# LaunchPad_Connectors.net
KiCad netlist of a schematic drawn in Altium Designer
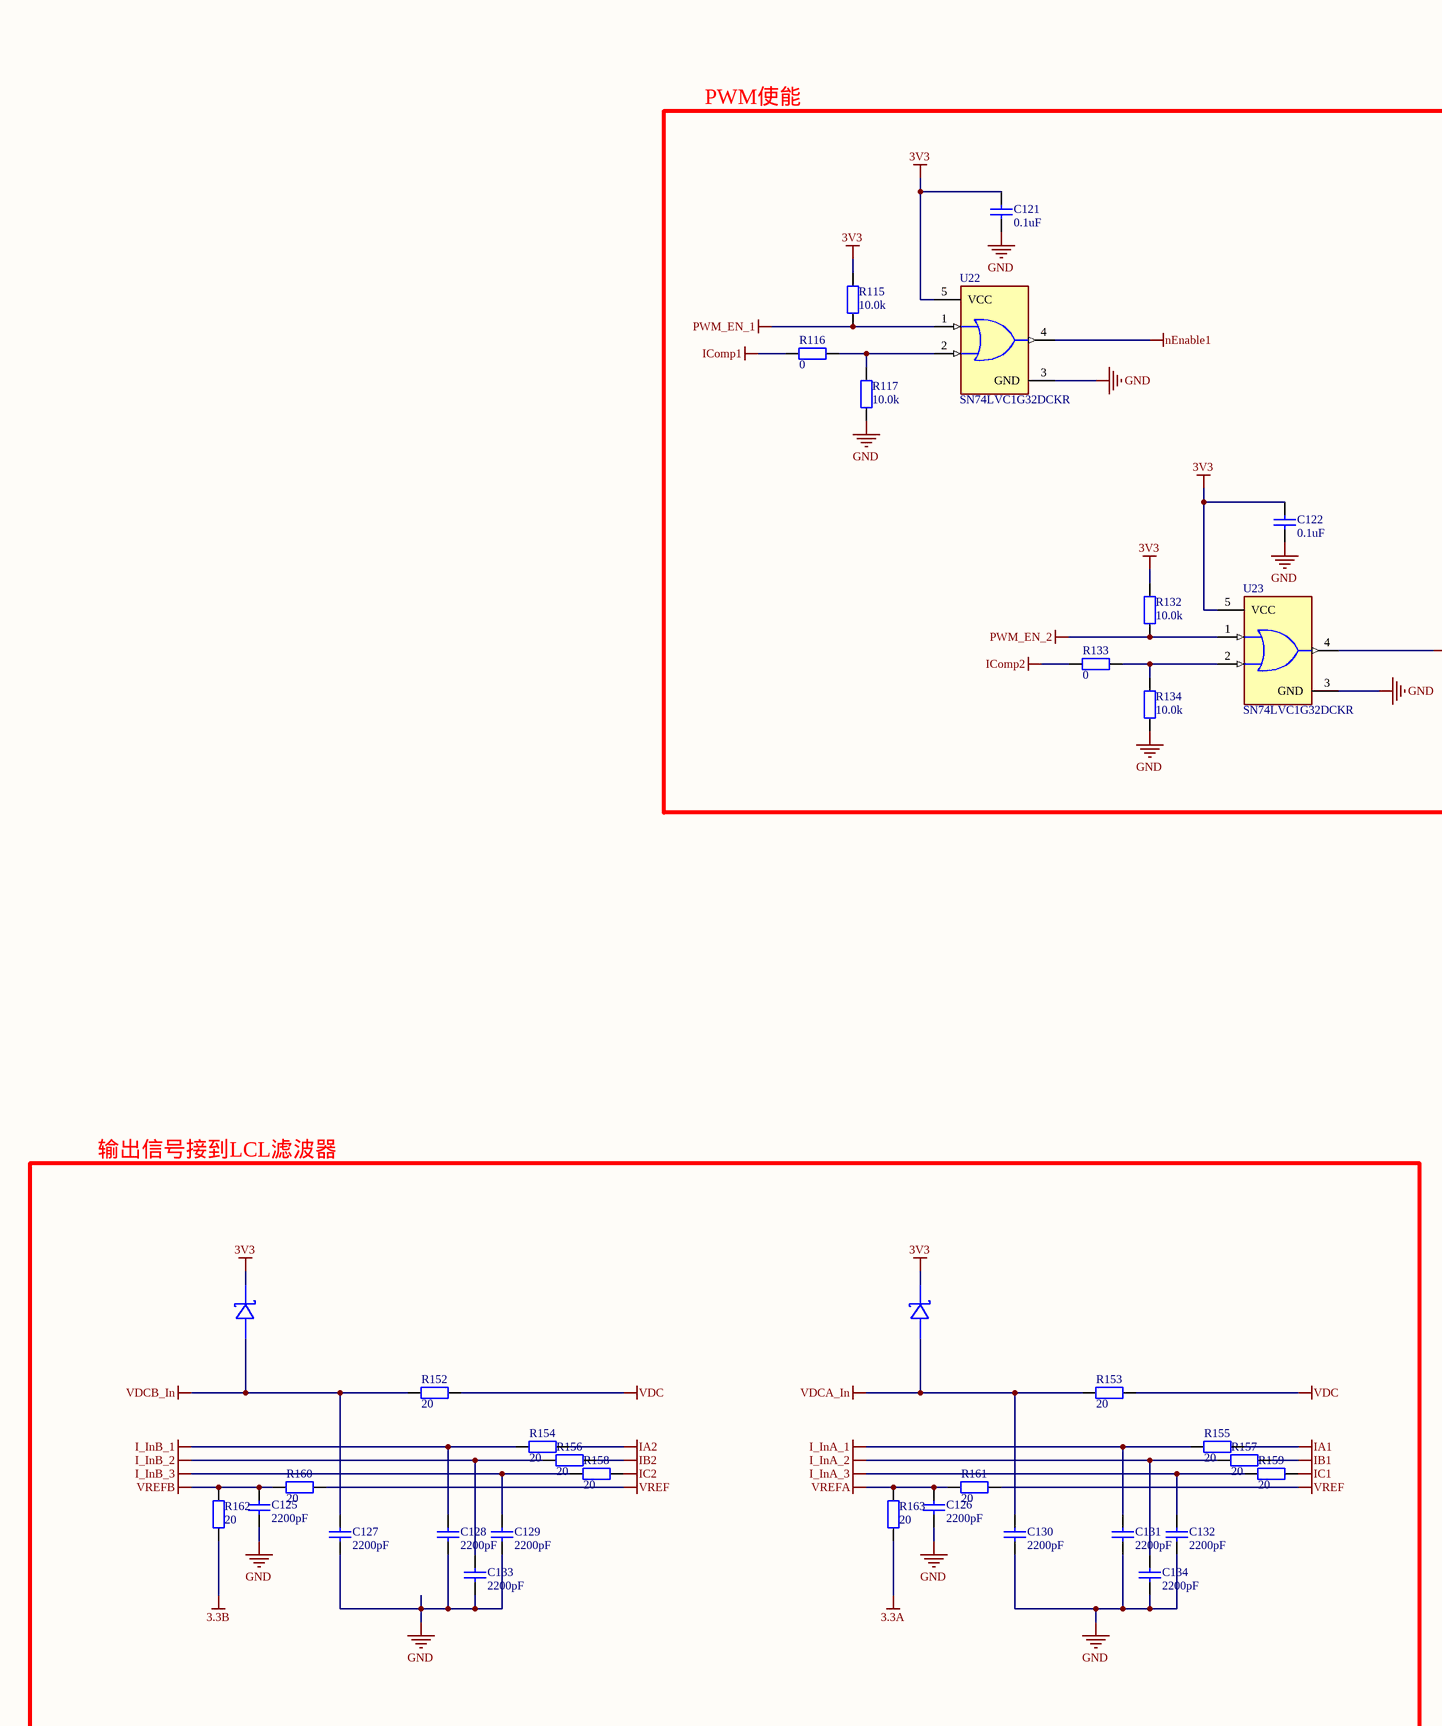
[diagram p0: LaunchPad Connectors.SchDoc, left]
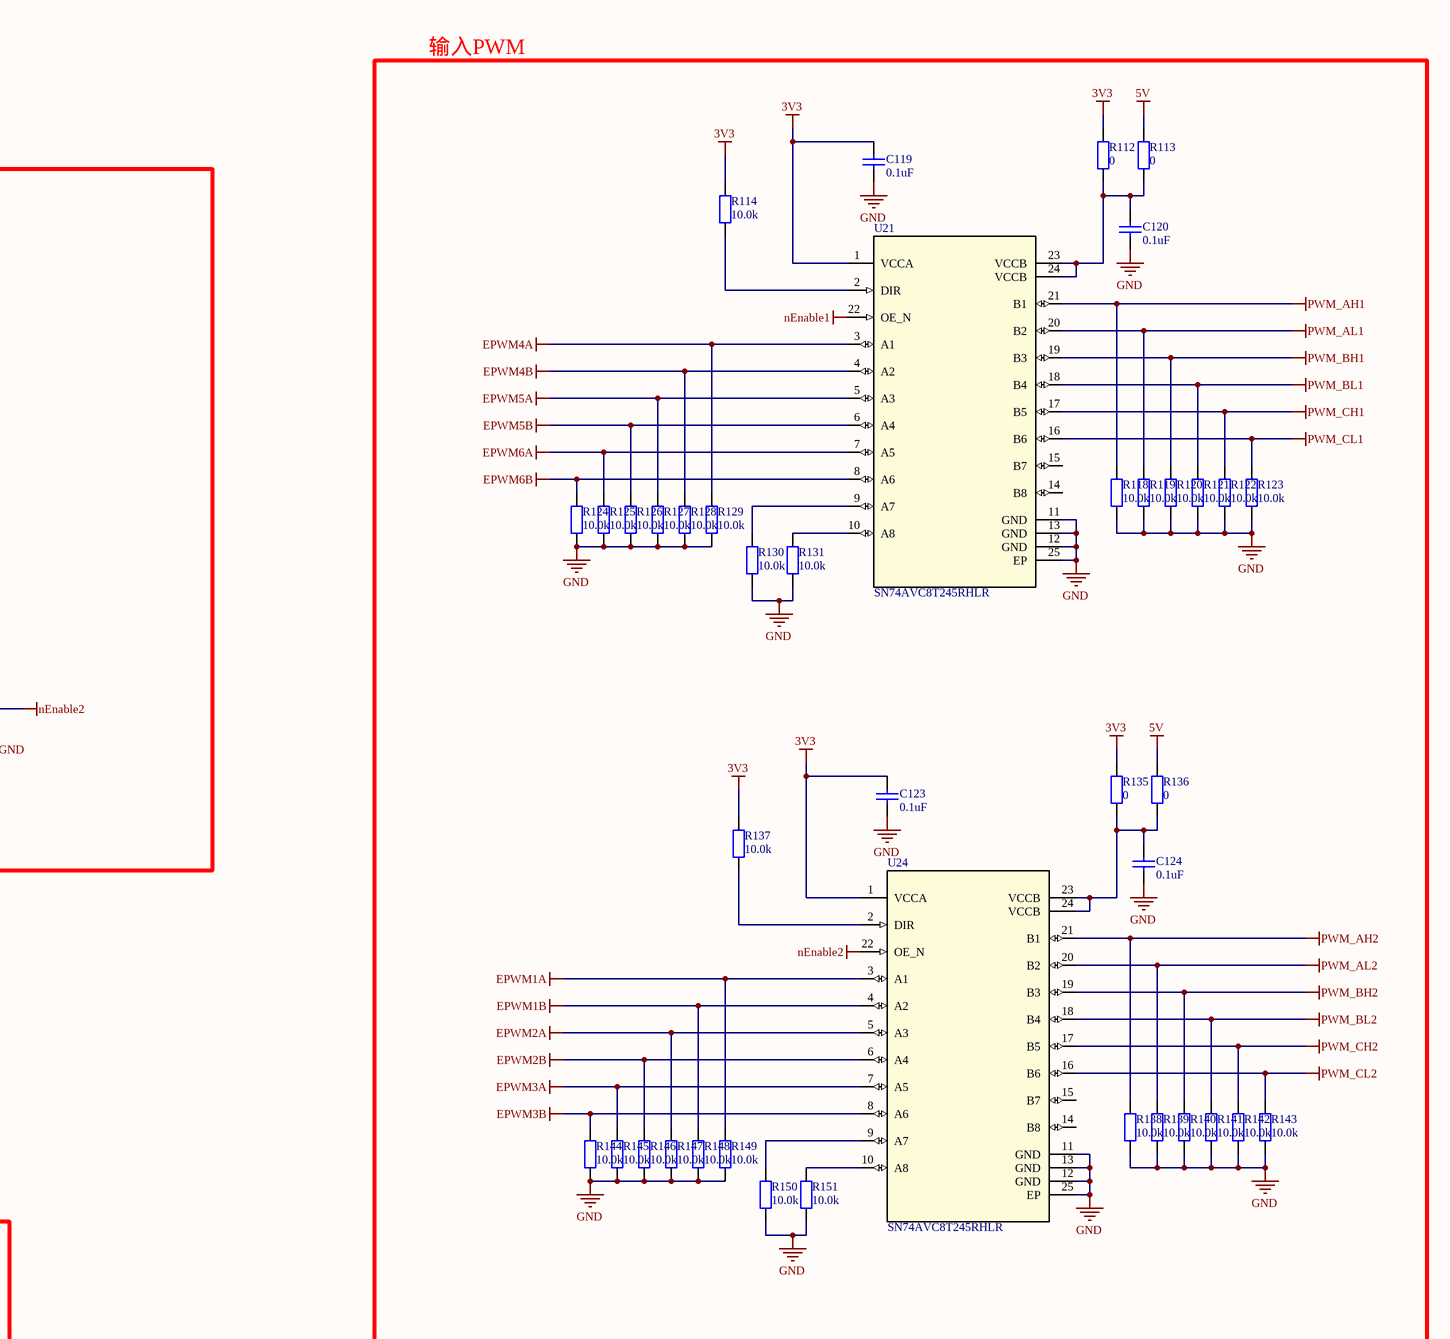
[diagram p1: LaunchPad Connectors.SchDoc, right]

(export (version "E")
  (design (tool "Eeschema 10.0.6"))
  (components
    (comp (ref "C119")
      (value "0.1uF")
      (footprint "CAPC1608X06N")
      (description "Capacitor")
      (fields (field (name "PUBLISHER") "Altium Limited"))
      (libsource (lib "Simscale") (part "Cap"))
    )
    (comp (ref "C120")
      (value "0.1uF")
      (footprint "CAPC1608X06N")
      (description "Capacitor")
      (fields (field (name "PUBLISHER") "Altium Limited"))
      (libsource (lib "Simscale") (part "Cap"))
    )
    (comp (ref "C121")
      (value "0.1uF")
      (footprint "CAPC1608X06N")
      (description "Capacitor")
      (fields (field (name "PUBLISHER") "Altium Limited"))
      (libsource (lib "Simscale") (part "Cap"))
    )
    (comp (ref "C122")
      (value "0.1uF")
      (footprint "CAPC1608X06N")
      (description "Capacitor")
      (fields (field (name "PUBLISHER") "Altium Limited"))
      (libsource (lib "Simscale") (part "Cap"))
    )
    (comp (ref "C123")
      (value "0.1uF")
      (footprint "CAPC1608X06N")
      (description "Capacitor")
      (fields (field (name "PUBLISHER") "Altium Limited"))
      (libsource (lib "Simscale") (part "Cap"))
    )
    (comp (ref "C124")
      (value "0.1uF")
      (footprint "CAPC1608X06N")
      (description "Capacitor")
      (fields (field (name "PUBLISHER") "Altium Limited"))
      (libsource (lib "Simscale") (part "Cap"))
    )
    (comp (ref "C125")
      (value "2200pF")
      (footprint "CAPC1608X06N")
      (description "Capacitor")
      (fields (field (name "PUBLISHER") "Altium Limited"))
      (libsource (lib "Simscale") (part "Cap"))
    )
    (comp (ref "C126")
      (value "2200pF")
      (footprint "CAPC1608X06N")
      (description "Capacitor")
      (fields (field (name "PUBLISHER") "Altium Limited"))
      (libsource (lib "Simscale") (part "Cap"))
    )
    (comp (ref "C127")
      (value "2200pF")
      (footprint "CAPC1608X06N")
      (description "Capacitor")
      (fields (field (name "PUBLISHER") "Altium Limited"))
      (libsource (lib "Simscale") (part "Cap"))
    )
    (comp (ref "C128")
      (value "2200pF")
      (footprint "CAPC1608X06N")
      (description "Capacitor")
      (fields (field (name "PUBLISHER") "Altium Limited"))
      (libsource (lib "Simscale") (part "Cap"))
    )
    (comp (ref "C129")
      (value "2200pF")
      (footprint "CAPC1608X06N")
      (description "Capacitor")
      (fields (field (name "PUBLISHER") "Altium Limited"))
      (libsource (lib "Simscale") (part "Cap"))
    )
    (comp (ref "C130")
      (value "2200pF")
      (footprint "CAPC1608X06N")
      (description "Capacitor")
      (fields (field (name "PUBLISHER") "Altium Limited"))
      (libsource (lib "Simscale") (part "Cap"))
    )
    (comp (ref "C131")
      (value "2200pF")
      (footprint "CAPC1608X06N")
      (description "Capacitor")
      (fields (field (name "PUBLISHER") "Altium Limited"))
      (libsource (lib "Simscale") (part "Cap"))
    )
    (comp (ref "C132")
      (value "2200pF")
      (footprint "CAPC1608X06N")
      (description "Capacitor")
      (fields (field (name "PUBLISHER") "Altium Limited"))
      (libsource (lib "Simscale") (part "Cap"))
    )
    (comp (ref "C133")
      (value "2200pF")
      (footprint "CAPC1608X06N")
      (description "Capacitor")
      (fields (field (name "PUBLISHER") "Altium Limited"))
      (libsource (lib "Simscale") (part "Cap"))
    )
    (comp (ref "C134")
      (value "2200pF")
      (footprint "CAPC1608X06N")
      (description "Capacitor")
      (fields (field (name "PUBLISHER") "Altium Limited"))
      (libsource (lib "Simscale") (part "Cap"))
    )
    (comp (ref "D1")
      (value "1PS79SB70,115")
      (footprint "SOD-523_L1.2-W0.8-LS1.6-RD")
      (fields (field (name "MANUFACTURER") "Nexperia(安世)"))
      (libsource (lib "1PS79SB70,1151_1PS79SB70,115.schdoc") (part "1PS79SB70,115"))
    )
    (comp (ref "D2")
      (value "1PS79SB70,115")
      (footprint "SOD-523_L1.2-W0.8-LS1.6-RD")
      (fields (field (name "MANUFACTURER") "Nexperia(安世)"))
      (libsource (lib "1PS79SB70,1151_1PS79SB70,115.schdoc") (part "1PS79SB70,115"))
    )
    (comp (ref "R112")
      (value "0")
      (footprint "RESC1608X05N")
      (description "Resistor 0402")
      (fields (field (name "PUBLISHER") "Altium Limited"))
      (libsource (lib "Soardra") (part "Res"))
    )
    (comp (ref "R113")
      (value "0")
      (footprint "RESC1608X05N")
      (description "Resistor 0402")
      (fields (field (name "PUBLISHER") "Altium Limited"))
      (libsource (lib "Soardra") (part "Res"))
    )
    (comp (ref "R114")
      (value "10.0k")
      (footprint "RESC1608X05N")
      (description "贴片电阻")
      (libsource (lib "") (part "0603 100KΩ (1003) 1%_4_2"))
    )
    (comp (ref "R115")
      (value "10.0k")
      (footprint "RESC1608X05N")
      (description "贴片电阻")
      (libsource (lib "") (part "0603 100KΩ (1003) 1%_4_2"))
    )
    (comp (ref "R116")
      (value "0")
      (footprint "RESC1608X05N")
      (description "贴片电阻")
      (libsource (lib "") (part "0603 100KΩ (1003) 1%_4_3"))
    )
    (comp (ref "R117")
      (value "10.0k")
      (footprint "RESC1608X05N")
      (description "贴片电阻")
      (libsource (lib "") (part "0603 100KΩ (1003) 1%_4_1"))
    )
    (comp (ref "R118")
      (value "10.0k")
      (footprint "RESC1608X05N")
      (description "贴片电阻")
      (libsource (lib "") (part "0603 100KΩ (1003) 1%_4_2"))
    )
    (comp (ref "R119")
      (value "10.0k")
      (footprint "RESC1608X05N")
      (description "贴片电阻")
      (libsource (lib "") (part "0603 100KΩ (1003) 1%_4_2"))
    )
    (comp (ref "R120")
      (value "10.0k")
      (footprint "RESC1608X05N")
      (description "贴片电阻")
      (libsource (lib "") (part "0603 100KΩ (1003) 1%_4_2"))
    )
    (comp (ref "R121")
      (value "10.0k")
      (footprint "RESC1608X05N")
      (description "贴片电阻")
      (libsource (lib "") (part "0603 100KΩ (1003) 1%_4_2"))
    )
    (comp (ref "R122")
      (value "10.0k")
      (footprint "RESC1608X05N")
      (description "贴片电阻")
      (libsource (lib "") (part "0603 100KΩ (1003) 1%_4_2"))
    )
    (comp (ref "R123")
      (value "10.0k")
      (footprint "RESC1608X05N")
      (description "贴片电阻")
      (libsource (lib "") (part "0603 100KΩ (1003) 1%_4_2"))
    )
    (comp (ref "R124")
      (value "10.0k")
      (footprint "RESC1608X05N")
      (description "贴片电阻")
      (libsource (lib "") (part "0603 100KΩ (1003) 1%_4_1"))
    )
    (comp (ref "R125")
      (value "10.0k")
      (footprint "RESC1608X05N")
      (description "贴片电阻")
      (libsource (lib "") (part "0603 100KΩ (1003) 1%_4_1"))
    )
    (comp (ref "R126")
      (value "10.0k")
      (footprint "RESC1608X05N")
      (description "贴片电阻")
      (libsource (lib "") (part "0603 100KΩ (1003) 1%_4_1"))
    )
    (comp (ref "R127")
      (value "10.0k")
      (footprint "RESC1608X05N")
      (description "贴片电阻")
      (libsource (lib "") (part "0603 100KΩ (1003) 1%_4_2"))
    )
    (comp (ref "R128")
      (value "10.0k")
      (footprint "RESC1608X05N")
      (description "贴片电阻")
      (libsource (lib "") (part "0603 100KΩ (1003) 1%_4_1"))
    )
    (comp (ref "R129")
      (value "10.0k")
      (footprint "RESC1608X05N")
      (description "贴片电阻")
      (libsource (lib "") (part "0603 100KΩ (1003) 1%_4_1"))
    )
    (comp (ref "R130")
      (value "10.0k")
      (footprint "RESC1608X05N")
      (description "贴片电阻")
      (libsource (lib "") (part "0603 100KΩ (1003) 1%_4_2"))
    )
    (comp (ref "R131")
      (value "10.0k")
      (footprint "RESC1608X05N")
      (description "贴片电阻")
      (libsource (lib "") (part "0603 100KΩ (1003) 1%_4_2"))
    )
    (comp (ref "R132")
      (value "10.0k")
      (footprint "RESC1608X05N")
      (description "贴片电阻")
      (libsource (lib "") (part "0603 100KΩ (1003) 1%_4_2"))
    )
    (comp (ref "R133")
      (value "0")
      (footprint "RESC1608X05N")
      (description "贴片电阻")
      (libsource (lib "") (part "0603 100KΩ (1003) 1%_4_3"))
    )
    (comp (ref "R134")
      (value "10.0k")
      (footprint "RESC1608X05N")
      (description "贴片电阻")
      (libsource (lib "") (part "0603 100KΩ (1003) 1%_4_1"))
    )
    (comp (ref "R135")
      (value "0")
      (footprint "RESC1608X05N")
      (description "Resistor 0402")
      (fields (field (name "PUBLISHER") "Altium Limited"))
      (libsource (lib "Soardra") (part "Res"))
    )
    (comp (ref "R136")
      (value "0")
      (footprint "RESC1608X05N")
      (description "Resistor 0402")
      (fields (field (name "PUBLISHER") "Altium Limited"))
      (libsource (lib "Soardra") (part "Res"))
    )
    (comp (ref "R137")
      (value "10.0k")
      (footprint "RESC1608X05N")
      (description "贴片电阻")
      (libsource (lib "") (part "0603 100KΩ (1003) 1%_4_2"))
    )
    (comp (ref "R138")
      (value "10.0k")
      (footprint "RESC1608X05N")
      (description "贴片电阻")
      (libsource (lib "") (part "0603 100KΩ (1003) 1%_4_2"))
    )
    (comp (ref "R139")
      (value "10.0k")
      (footprint "RESC1608X05N")
      (description "贴片电阻")
      (libsource (lib "") (part "0603 100KΩ (1003) 1%_4_2"))
    )
    (comp (ref "R140")
      (value "10.0k")
      (footprint "RESC1608X05N")
      (description "贴片电阻")
      (libsource (lib "") (part "0603 100KΩ (1003) 1%_4_2"))
    )
    (comp (ref "R141")
      (value "10.0k")
      (footprint "RESC1608X05N")
      (description "贴片电阻")
      (libsource (lib "") (part "0603 100KΩ (1003) 1%_4_2"))
    )
    (comp (ref "R142")
      (value "10.0k")
      (footprint "RESC1608X05N")
      (description "贴片电阻")
      (libsource (lib "") (part "0603 100KΩ (1003) 1%_4_2"))
    )
    (comp (ref "R143")
      (value "10.0k")
      (footprint "RESC1608X05N")
      (description "贴片电阻")
      (libsource (lib "") (part "0603 100KΩ (1003) 1%_4_2"))
    )
    (comp (ref "R144")
      (value "10.0k")
      (footprint "RESC1608X05N")
      (description "贴片电阻")
      (libsource (lib "") (part "0603 100KΩ (1003) 1%_4_1"))
    )
    (comp (ref "R145")
      (value "10.0k")
      (footprint "RESC1608X05N")
      (description "贴片电阻")
      (libsource (lib "") (part "0603 100KΩ (1003) 1%_4_1"))
    )
    (comp (ref "R146")
      (value "10.0k")
      (footprint "RESC1608X05N")
      (description "贴片电阻")
      (libsource (lib "") (part "0603 100KΩ (1003) 1%_4_1"))
    )
    (comp (ref "R147")
      (value "10.0k")
      (footprint "RESC1608X05N")
      (description "贴片电阻")
      (libsource (lib "") (part "0603 100KΩ (1003) 1%_4_2"))
    )
    (comp (ref "R148")
      (value "10.0k")
      (footprint "RESC1608X05N")
      (description "贴片电阻")
      (libsource (lib "") (part "0603 100KΩ (1003) 1%_4_1"))
    )
    (comp (ref "R149")
      (value "10.0k")
      (footprint "RESC1608X05N")
      (description "贴片电阻")
      (libsource (lib "") (part "0603 100KΩ (1003) 1%_4_1"))
    )
    (comp (ref "R150")
      (value "10.0k")
      (footprint "RESC1608X05N")
      (description "贴片电阻")
      (libsource (lib "") (part "0603 100KΩ (1003) 1%_4_2"))
    )
    (comp (ref "R151")
      (value "10.0k")
      (footprint "RESC1608X05N")
      (description "贴片电阻")
      (libsource (lib "") (part "0603 100KΩ (1003) 1%_4_2"))
    )
    (comp (ref "R152")
      (value "20")
      (footprint "RESC1608X05N")
      (description "贴片电阻")
      (libsource (lib "Simscale") (part "0603 100KΩ (1003) 1%_4"))
    )
    (comp (ref "R153")
      (value "20")
      (footprint "RESC1608X05N")
      (description "贴片电阻")
      (libsource (lib "Simscale") (part "0603 100KΩ (1003) 1%_4"))
    )
    (comp (ref "R154")
      (value "20")
      (footprint "RESC1608X05N")
      (description "贴片电阻")
      (libsource (lib "Simscale") (part "0603 100KΩ (1003) 1%_4"))
    )
    (comp (ref "R155")
      (value "20")
      (footprint "RESC1608X05N")
      (description "贴片电阻")
      (libsource (lib "Simscale") (part "0603 100KΩ (1003) 1%_4"))
    )
    (comp (ref "R156")
      (value "20")
      (footprint "RESC1608X05N")
      (description "贴片电阻")
      (libsource (lib "Simscale") (part "0603 100KΩ (1003) 1%_4"))
    )
    (comp (ref "R157")
      (value "20")
      (footprint "RESC1608X05N")
      (description "贴片电阻")
      (libsource (lib "Simscale") (part "0603 100KΩ (1003) 1%_4"))
    )
    (comp (ref "R158")
      (value "20")
      (footprint "RESC1608X05N")
      (description "贴片电阻")
      (libsource (lib "Simscale") (part "0603 100KΩ (1003) 1%_4"))
    )
    (comp (ref "R159")
      (value "20")
      (footprint "RESC1608X05N")
      (description "贴片电阻")
      (libsource (lib "Simscale") (part "0603 100KΩ (1003) 1%_4"))
    )
    (comp (ref "R160")
      (value "20")
      (footprint "RESC1608X05N")
      (description "贴片电阻")
      (libsource (lib "Simscale") (part "0603 100KΩ (1003) 1%_4"))
    )
    (comp (ref "R161")
      (value "20")
      (footprint "RESC1608X05N")
      (description "贴片电阻")
      (libsource (lib "Simscale") (part "0603 100KΩ (1003) 1%_4"))
    )
    (comp (ref "R162")
      (value "20")
      (footprint "RESC1608X05N")
      (description "贴片电阻")
      (libsource (lib "") (part "0603 100KΩ (1003) 1%_4_2"))
    )
    (comp (ref "R163")
      (value "20")
      (footprint "RESC1608X05N")
      (description "贴片电阻")
      (libsource (lib "") (part "0603 100KΩ (1003) 1%_4_2"))
    )
    (comp (ref "U21")
      (value "SN74AVC8T245RHLR")
      (footprint "RHL0024A")
      (description "No Description Available")
      (fields
        (field (name "PARTNUMBER") "SN74AVC8T245RHL")
        (field (name "MANUFACTURER") "Texas Instruments")
        (field (name "COPYRIGHT") "Copyright (C) 2024 Ultra Librarian. All rights reserved.")
      )
      (libsource (lib "aaa1") (part "SN74AVC8T245RHLR"))
    )
    (comp (ref "U22")
      (value "SN74LVC1G32DCKR")
      (footprint "FP-DCK0005A-IPC_A")
      (description "IC GATE OR 1CH 2-INP SC70-5")
      (libsource (lib "Altium Content Vault") (part "9a4003fa4a62225b3c2fa1ca1eebe37"))
    )
    (comp (ref "U23")
      (value "SN74LVC1G32DCKR")
      (footprint "FP-DCK0005A-IPC_A")
      (description "IC GATE OR 1CH 2-INP SC70-5")
      (libsource (lib "Altium Content Vault") (part "9a4003fa4a62225b3c2fa1ca1eebe37"))
    )
    (comp (ref "U24")
      (value "SN74AVC8T245RHLR")
      (footprint "RHL0024A")
      (description "No Description Available")
      (fields
        (field (name "PARTNUMBER") "SN74AVC8T245RHL")
        (field (name "MANUFACTURER") "Texas Instruments")
        (field (name "COPYRIGHT") "Copyright (C) 2024 Ultra Librarian. All rights reserved.")
      )
      (libsource (lib "aaa1") (part "SN74AVC8T245RHLR"))
    )
  )
  (nets
    (net (code "1") (name "3.3A") (class "Default")
      (node (ref "R163") (pin "2") (pinfunction "2_2") (pintype "passive"))
    )
    (net (code "2") (name "3.3B") (class "Default")
      (node (ref "R162") (pin "2") (pinfunction "2_2") (pintype "passive"))
    )
    (net (code "3") (name "3V3") (class "Default")
      (node (ref "C119") (pin "1") (pinfunction "1_1") (pintype "passive"))
      (node (ref "C121") (pin "1") (pinfunction "1_1") (pintype "passive"))
      (node (ref "C122") (pin "1") (pinfunction "1_1") (pintype "passive"))
      (node (ref "C123") (pin "1") (pinfunction "1_1") (pintype "passive"))
      (node (ref "D1") (pin "1") (pinfunction "K_1") (pintype "passive"))
      (node (ref "D2") (pin "1") (pinfunction "K_1") (pintype "passive"))
      (node (ref "R112") (pin "2") (pinfunction "2_2") (pintype "passive"))
      (node (ref "R114") (pin "1") (pinfunction "1_1") (pintype "passive"))
      (node (ref "R115") (pin "1") (pinfunction "1_1") (pintype "passive"))
      (node (ref "R132") (pin "1") (pinfunction "1_1") (pintype "passive"))
      (node (ref "R135") (pin "2") (pinfunction "2_2") (pintype "passive"))
      (node (ref "R137") (pin "1") (pinfunction "1_1") (pintype "passive"))
      (node (ref "U21") (pin "1") (pinfunction "VCCA_1") (pintype "power_in"))
      (node (ref "U22") (pin "5") (pinfunction "VCC_5") (pintype "power_in"))
      (node (ref "U23") (pin "5") (pinfunction "VCC_5") (pintype "power_in"))
      (node (ref "U24") (pin "1") (pinfunction "VCCA_1") (pintype "power_in"))
    )
    (net (code "4") (name "5V") (class "Default")
      (node (ref "R113") (pin "2") (pinfunction "2_2") (pintype "passive"))
      (node (ref "R136") (pin "2") (pinfunction "2_2") (pintype "passive"))
    )
    (net (code "5") (name "EPWM1A") (class "Default")
      (node (ref "R149") (pin "2") (pinfunction "2_2") (pintype "passive"))
      (node (ref "U24") (pin "3") (pinfunction "A1_3") (pintype "bidirectional"))
    )
    (net (code "6") (name "EPWM1B") (class "Default")
      (node (ref "R148") (pin "2") (pinfunction "2_2") (pintype "passive"))
      (node (ref "U24") (pin "4") (pinfunction "A2_4") (pintype "bidirectional"))
    )
    (net (code "7") (name "EPWM2A") (class "Default")
      (node (ref "R147") (pin "1") (pinfunction "1_1") (pintype "passive"))
      (node (ref "U24") (pin "5") (pinfunction "A3_5") (pintype "bidirectional"))
    )
    (net (code "8") (name "EPWM2B") (class "Default")
      (node (ref "R146") (pin "2") (pinfunction "2_2") (pintype "passive"))
      (node (ref "U24") (pin "6") (pinfunction "A4_6") (pintype "bidirectional"))
    )
    (net (code "9") (name "EPWM3A") (class "Default")
      (node (ref "R145") (pin "2") (pinfunction "2_2") (pintype "passive"))
      (node (ref "U24") (pin "7") (pinfunction "A5_7") (pintype "bidirectional"))
    )
    (net (code "10") (name "EPWM3B") (class "Default")
      (node (ref "R144") (pin "2") (pinfunction "2_2") (pintype "passive"))
      (node (ref "U24") (pin "8") (pinfunction "A6_8") (pintype "bidirectional"))
    )
    (net (code "11") (name "EPWM4A") (class "Default")
      (node (ref "R129") (pin "2") (pinfunction "2_2") (pintype "passive"))
      (node (ref "U21") (pin "3") (pinfunction "A1_3") (pintype "bidirectional"))
    )
    (net (code "12") (name "EPWM4B") (class "Default")
      (node (ref "R128") (pin "2") (pinfunction "2_2") (pintype "passive"))
      (node (ref "U21") (pin "4") (pinfunction "A2_4") (pintype "bidirectional"))
    )
    (net (code "13") (name "EPWM5A") (class "Default")
      (node (ref "R127") (pin "1") (pinfunction "1_1") (pintype "passive"))
      (node (ref "U21") (pin "5") (pinfunction "A3_5") (pintype "bidirectional"))
    )
    (net (code "14") (name "EPWM5B") (class "Default")
      (node (ref "R126") (pin "2") (pinfunction "2_2") (pintype "passive"))
      (node (ref "U21") (pin "6") (pinfunction "A4_6") (pintype "bidirectional"))
    )
    (net (code "15") (name "EPWM6A") (class "Default")
      (node (ref "R125") (pin "2") (pinfunction "2_2") (pintype "passive"))
      (node (ref "U21") (pin "7") (pinfunction "A5_7") (pintype "bidirectional"))
    )
    (net (code "16") (name "EPWM6B") (class "Default")
      (node (ref "R124") (pin "2") (pinfunction "2_2") (pintype "passive"))
      (node (ref "U21") (pin "8") (pinfunction "A6_8") (pintype "bidirectional"))
    )
    (net (code "17") (name "GND") (class "Default")
      (node (ref "C119") (pin "2") (pinfunction "2_2") (pintype "passive"))
      (node (ref "C120") (pin "2") (pinfunction "2_2") (pintype "passive"))
      (node (ref "C121") (pin "2") (pinfunction "2_2") (pintype "passive"))
      (node (ref "C122") (pin "2") (pinfunction "2_2") (pintype "passive"))
      (node (ref "C123") (pin "2") (pinfunction "2_2") (pintype "passive"))
      (node (ref "C124") (pin "2") (pinfunction "2_2") (pintype "passive"))
      (node (ref "C125") (pin "2") (pinfunction "2_2") (pintype "passive"))
      (node (ref "C126") (pin "2") (pinfunction "2_2") (pintype "passive"))
      (node (ref "C127") (pin "2") (pinfunction "2_2") (pintype "passive"))
      (node (ref "C128") (pin "2") (pinfunction "2_2") (pintype "passive"))
      (node (ref "C129") (pin "2") (pinfunction "2_2") (pintype "passive"))
      (node (ref "C130") (pin "2") (pinfunction "2_2") (pintype "passive"))
      (node (ref "C131") (pin "2") (pinfunction "2_2") (pintype "passive"))
      (node (ref "C132") (pin "2") (pinfunction "2_2") (pintype "passive"))
      (node (ref "C133") (pin "2") (pinfunction "2_2") (pintype "passive"))
      (node (ref "C134") (pin "2") (pinfunction "2_2") (pintype "passive"))
      (node (ref "R117") (pin "1") (pinfunction "1_1") (pintype "passive"))
      (node (ref "R118") (pin "2") (pinfunction "2_2") (pintype "passive"))
      (node (ref "R119") (pin "2") (pinfunction "2_2") (pintype "passive"))
      (node (ref "R120") (pin "2") (pinfunction "2_2") (pintype "passive"))
      (node (ref "R121") (pin "2") (pinfunction "2_2") (pintype "passive"))
      (node (ref "R122") (pin "2") (pinfunction "2_2") (pintype "passive"))
      (node (ref "R123") (pin "2") (pinfunction "2_2") (pintype "passive"))
      (node (ref "R124") (pin "1") (pinfunction "1_1") (pintype "passive"))
      (node (ref "R125") (pin "1") (pinfunction "1_1") (pintype "passive"))
      (node (ref "R126") (pin "1") (pinfunction "1_1") (pintype "passive"))
      (node (ref "R127") (pin "2") (pinfunction "2_2") (pintype "passive"))
      (node (ref "R128") (pin "1") (pinfunction "1_1") (pintype "passive"))
      (node (ref "R129") (pin "1") (pinfunction "1_1") (pintype "passive"))
      (node (ref "R130") (pin "2") (pinfunction "2_2") (pintype "passive"))
      (node (ref "R131") (pin "2") (pinfunction "2_2") (pintype "passive"))
      (node (ref "R134") (pin "1") (pinfunction "1_1") (pintype "passive"))
      (node (ref "R138") (pin "2") (pinfunction "2_2") (pintype "passive"))
      (node (ref "R139") (pin "2") (pinfunction "2_2") (pintype "passive"))
      (node (ref "R140") (pin "2") (pinfunction "2_2") (pintype "passive"))
      (node (ref "R141") (pin "2") (pinfunction "2_2") (pintype "passive"))
      (node (ref "R142") (pin "2") (pinfunction "2_2") (pintype "passive"))
      (node (ref "R143") (pin "2") (pinfunction "2_2") (pintype "passive"))
      (node (ref "R144") (pin "1") (pinfunction "1_1") (pintype "passive"))
      (node (ref "R145") (pin "1") (pinfunction "1_1") (pintype "passive"))
      (node (ref "R146") (pin "1") (pinfunction "1_1") (pintype "passive"))
      (node (ref "R147") (pin "2") (pinfunction "2_2") (pintype "passive"))
      (node (ref "R148") (pin "1") (pinfunction "1_1") (pintype "passive"))
      (node (ref "R149") (pin "1") (pinfunction "1_1") (pintype "passive"))
      (node (ref "R150") (pin "2") (pinfunction "2_2") (pintype "passive"))
      (node (ref "R151") (pin "2") (pinfunction "2_2") (pintype "passive"))
      (node (ref "U21") (pin "11") (pinfunction "GND_11") (pintype "power_in"))
      (node (ref "U21") (pin "12") (pinfunction "GND_12") (pintype "power_in"))
      (node (ref "U21") (pin "13") (pinfunction "GND_13") (pintype "power_in"))
      (node (ref "U21") (pin "25") (pinfunction "EP_25") (pintype "passive"))
      (node (ref "U22") (pin "3") (pinfunction "GND_3") (pintype "power_in"))
      (node (ref "U23") (pin "3") (pinfunction "GND_3") (pintype "power_in"))
      (node (ref "U24") (pin "11") (pinfunction "GND_11") (pintype "power_in"))
      (node (ref "U24") (pin "12") (pinfunction "GND_12") (pintype "power_in"))
      (node (ref "U24") (pin "13") (pinfunction "GND_13") (pintype "power_in"))
      (node (ref "U24") (pin "25") (pinfunction "EP_25") (pintype "passive"))
    )
    (net (code "18") (name "IA1") (class "Default")
      (node (ref "R155") (pin "1") (pinfunction "1_1") (pintype "passive"))
    )
    (net (code "19") (name "IA2") (class "Default")
      (node (ref "R154") (pin "1") (pinfunction "1_1") (pintype "passive"))
    )
    (net (code "20") (name "IB1") (class "Default")
      (node (ref "R157") (pin "1") (pinfunction "1_1") (pintype "passive"))
    )
    (net (code "21") (name "IB2") (class "Default")
      (node (ref "R156") (pin "1") (pinfunction "1_1") (pintype "passive"))
    )
    (net (code "22") (name "IC1") (class "Default")
      (node (ref "R159") (pin "1") (pinfunction "1_1") (pintype "passive"))
    )
    (net (code "23") (name "IC2") (class "Default")
      (node (ref "R158") (pin "1") (pinfunction "1_1") (pintype "passive"))
    )
    (net (code "24") (name "IComp1") (class "Default")
      (node (ref "R116") (pin "1") (pinfunction "1_1") (pintype "passive"))
    )
    (net (code "25") (name "IComp2") (class "Default")
      (node (ref "R133") (pin "1") (pinfunction "1_1") (pintype "passive"))
    )
    (net (code "26") (name "I_InA_1") (class "Default")
      (node (ref "C131") (pin "1") (pinfunction "1_1") (pintype "passive"))
      (node (ref "R155") (pin "2") (pinfunction "2_2") (pintype "passive"))
    )
    (net (code "27") (name "I_InA_2") (class "Default")
      (node (ref "C134") (pin "1") (pinfunction "1_1") (pintype "passive"))
      (node (ref "R157") (pin "2") (pinfunction "2_2") (pintype "passive"))
    )
    (net (code "28") (name "I_InA_3") (class "Default")
      (node (ref "C132") (pin "1") (pinfunction "1_1") (pintype "passive"))
      (node (ref "R159") (pin "2") (pinfunction "2_2") (pintype "passive"))
    )
    (net (code "29") (name "I_InB_1") (class "Default")
      (node (ref "C128") (pin "1") (pinfunction "1_1") (pintype "passive"))
      (node (ref "R154") (pin "2") (pinfunction "2_2") (pintype "passive"))
    )
    (net (code "30") (name "I_InB_2") (class "Default")
      (node (ref "C133") (pin "1") (pinfunction "1_1") (pintype "passive"))
      (node (ref "R156") (pin "2") (pinfunction "2_2") (pintype "passive"))
    )
    (net (code "31") (name "I_InB_3") (class "Default")
      (node (ref "C129") (pin "1") (pinfunction "1_1") (pintype "passive"))
      (node (ref "R158") (pin "2") (pinfunction "2_2") (pintype "passive"))
    )
    (net (code "32") (name "Net-(C120-Pad1)") (class "Default")
      (node (ref "C120") (pin "1") (pinfunction "1_1") (pintype "passive"))
      (node (ref "R112") (pin "1") (pinfunction "1_1") (pintype "passive"))
      (node (ref "R113") (pin "1") (pinfunction "1_1") (pintype "passive"))
      (node (ref "U21") (pin "23") (pinfunction "VCCB_23") (pintype "power_in"))
      (node (ref "U21") (pin "24") (pinfunction "VCCB_24") (pintype "power_in"))
    )
    (net (code "33") (name "Net-(C124-Pad1)") (class "Default")
      (node (ref "C124") (pin "1") (pinfunction "1_1") (pintype "passive"))
      (node (ref "R135") (pin "1") (pinfunction "1_1") (pintype "passive"))
      (node (ref "R136") (pin "1") (pinfunction "1_1") (pintype "passive"))
      (node (ref "U24") (pin "23") (pinfunction "VCCB_23") (pintype "power_in"))
      (node (ref "U24") (pin "24") (pinfunction "VCCB_24") (pintype "power_in"))
    )
    (net (code "34") (name "Net-(U21-A7)") (class "Default")
      (node (ref "R130") (pin "1") (pinfunction "1_1") (pintype "passive"))
      (node (ref "U21") (pin "9") (pinfunction "A7_9") (pintype "bidirectional"))
    )
    (net (code "35") (name "Net-(U21-A8)") (class "Default")
      (node (ref "R131") (pin "1") (pinfunction "1_1") (pintype "passive"))
      (node (ref "U21") (pin "10") (pinfunction "A8_10") (pintype "bidirectional"))
    )
    (net (code "36") (name "Net-(U21-DIR)") (class "Default")
      (node (ref "R114") (pin "2") (pinfunction "2_2") (pintype "passive"))
      (node (ref "U21") (pin "2") (pinfunction "DIR_2") (pintype "input"))
    )
    (net (code "37") (name "Net-(U22-B)") (class "Default")
      (node (ref "R116") (pin "2") (pinfunction "2_2") (pintype "passive"))
      (node (ref "R117") (pin "2") (pinfunction "2_2") (pintype "passive"))
      (node (ref "U22") (pin "2") (pinfunction "B_2") (pintype "input"))
    )
    (net (code "38") (name "Net-(U23-B)") (class "Default")
      (node (ref "R133") (pin "2") (pinfunction "2_2") (pintype "passive"))
      (node (ref "R134") (pin "2") (pinfunction "2_2") (pintype "passive"))
      (node (ref "U23") (pin "2") (pinfunction "B_2") (pintype "input"))
    )
    (net (code "39") (name "Net-(U24-A7)") (class "Default")
      (node (ref "R150") (pin "1") (pinfunction "1_1") (pintype "passive"))
      (node (ref "U24") (pin "9") (pinfunction "A7_9") (pintype "bidirectional"))
    )
    (net (code "40") (name "Net-(U24-A8)") (class "Default")
      (node (ref "R151") (pin "1") (pinfunction "1_1") (pintype "passive"))
      (node (ref "U24") (pin "10") (pinfunction "A8_10") (pintype "bidirectional"))
    )
    (net (code "41") (name "Net-(U24-DIR)") (class "Default")
      (node (ref "R137") (pin "2") (pinfunction "2_2") (pintype "passive"))
      (node (ref "U24") (pin "2") (pinfunction "DIR_2") (pintype "input"))
    )
    (net (code "42") (name "PWM_AH1") (class "Default")
      (node (ref "R118") (pin "1") (pinfunction "1_1") (pintype "passive"))
      (node (ref "U21") (pin "21") (pinfunction "B1_21") (pintype "bidirectional"))
    )
    (net (code "43") (name "PWM_AH2") (class "Default")
      (node (ref "R138") (pin "1") (pinfunction "1_1") (pintype "passive"))
      (node (ref "U24") (pin "21") (pinfunction "B1_21") (pintype "bidirectional"))
    )
    (net (code "44") (name "PWM_AL1") (class "Default")
      (node (ref "R119") (pin "1") (pinfunction "1_1") (pintype "passive"))
      (node (ref "U21") (pin "20") (pinfunction "B2_20") (pintype "bidirectional"))
    )
    (net (code "45") (name "PWM_AL2") (class "Default")
      (node (ref "R139") (pin "1") (pinfunction "1_1") (pintype "passive"))
      (node (ref "U24") (pin "20") (pinfunction "B2_20") (pintype "bidirectional"))
    )
    (net (code "46") (name "PWM_BH1") (class "Default")
      (node (ref "R120") (pin "1") (pinfunction "1_1") (pintype "passive"))
      (node (ref "U21") (pin "19") (pinfunction "B3_19") (pintype "bidirectional"))
    )
    (net (code "47") (name "PWM_BH2") (class "Default")
      (node (ref "R140") (pin "1") (pinfunction "1_1") (pintype "passive"))
      (node (ref "U24") (pin "19") (pinfunction "B3_19") (pintype "bidirectional"))
    )
    (net (code "48") (name "PWM_BL1") (class "Default")
      (node (ref "R121") (pin "1") (pinfunction "1_1") (pintype "passive"))
      (node (ref "U21") (pin "18") (pinfunction "B4_18") (pintype "bidirectional"))
    )
    (net (code "49") (name "PWM_BL2") (class "Default")
      (node (ref "R141") (pin "1") (pinfunction "1_1") (pintype "passive"))
      (node (ref "U24") (pin "18") (pinfunction "B4_18") (pintype "bidirectional"))
    )
    (net (code "50") (name "PWM_CH1") (class "Default")
      (node (ref "R122") (pin "1") (pinfunction "1_1") (pintype "passive"))
      (node (ref "U21") (pin "17") (pinfunction "B5_17") (pintype "bidirectional"))
    )
    (net (code "51") (name "PWM_CH2") (class "Default")
      (node (ref "R142") (pin "1") (pinfunction "1_1") (pintype "passive"))
      (node (ref "U24") (pin "17") (pinfunction "B5_17") (pintype "bidirectional"))
    )
    (net (code "52") (name "PWM_CL1") (class "Default")
      (node (ref "R123") (pin "1") (pinfunction "1_1") (pintype "passive"))
      (node (ref "U21") (pin "16") (pinfunction "B6_16") (pintype "bidirectional"))
    )
    (net (code "53") (name "PWM_CL2") (class "Default")
      (node (ref "R143") (pin "1") (pinfunction "1_1") (pintype "passive"))
      (node (ref "U24") (pin "16") (pinfunction "B6_16") (pintype "bidirectional"))
    )
    (net (code "54") (name "PWM_EN_1") (class "Default")
      (node (ref "R115") (pin "2") (pinfunction "2_2") (pintype "passive"))
      (node (ref "U22") (pin "1") (pinfunction "A_1") (pintype "input"))
    )
    (net (code "55") (name "PWM_EN_2") (class "Default")
      (node (ref "R132") (pin "2") (pinfunction "2_2") (pintype "passive"))
      (node (ref "U23") (pin "1") (pinfunction "A_1") (pintype "input"))
    )
    (net (code "56") (name "VDC") (class "Default")
      (node (ref "R152") (pin "1") (pinfunction "1_1") (pintype "passive"))
      (node (ref "R153") (pin "1") (pinfunction "1_1") (pintype "passive"))
    )
    (net (code "57") (name "VDCA_In") (class "Default")
      (node (ref "C130") (pin "1") (pinfunction "1_1") (pintype "passive"))
      (node (ref "D2") (pin "2") (pinfunction "A_2") (pintype "passive"))
      (node (ref "R153") (pin "2") (pinfunction "2_2") (pintype "passive"))
    )
    (net (code "58") (name "VDCB_In") (class "Default")
      (node (ref "C127") (pin "1") (pinfunction "1_1") (pintype "passive"))
      (node (ref "D1") (pin "2") (pinfunction "A_2") (pintype "passive"))
      (node (ref "R152") (pin "2") (pinfunction "2_2") (pintype "passive"))
    )
    (net (code "59") (name "VREF") (class "Default")
      (node (ref "R160") (pin "1") (pinfunction "1_1") (pintype "passive"))
      (node (ref "R161") (pin "1") (pinfunction "1_1") (pintype "passive"))
    )
    (net (code "60") (name "VREFA") (class "Default")
      (node (ref "C126") (pin "1") (pinfunction "1_1") (pintype "passive"))
      (node (ref "R161") (pin "2") (pinfunction "2_2") (pintype "passive"))
      (node (ref "R163") (pin "1") (pinfunction "1_1") (pintype "passive"))
    )
    (net (code "61") (name "VREFB") (class "Default")
      (node (ref "C125") (pin "1") (pinfunction "1_1") (pintype "passive"))
      (node (ref "R160") (pin "2") (pinfunction "2_2") (pintype "passive"))
      (node (ref "R162") (pin "1") (pinfunction "1_1") (pintype "passive"))
    )
    (net (code "62") (name "nEnable1") (class "Default")
      (node (ref "U21") (pin "22") (pinfunction "OE_N_22") (pintype "input"))
      (node (ref "U22") (pin "4") (pinfunction "Y_4") (pintype "output"))
    )
    (net (code "63") (name "nEnable2") (class "Default")
      (node (ref "U23") (pin "4") (pinfunction "Y_4") (pintype "output"))
      (node (ref "U24") (pin "22") (pinfunction "OE_N_22") (pintype "input"))
    )
    (net (code "64") (name "unconnected-(U21-B7-Pad15)") (class "Default")
      (node (ref "U21") (pin "15") (pinfunction "B7_15") (pintype "bidirectional"))
    )
    (net (code "65") (name "unconnected-(U21-B8-Pad14)") (class "Default")
      (node (ref "U21") (pin "14") (pinfunction "B8_14") (pintype "bidirectional"))
    )
    (net (code "66") (name "unconnected-(U24-B7-Pad15)") (class "Default")
      (node (ref "U24") (pin "15") (pinfunction "B7_15") (pintype "bidirectional"))
    )
    (net (code "67") (name "unconnected-(U24-B8-Pad14)") (class "Default")
      (node (ref "U24") (pin "14") (pinfunction "B8_14") (pintype "bidirectional"))
    )
  )
)
